# MI0283QT_v13.net
KiCad netlist of a schematic drawn in EAGLE
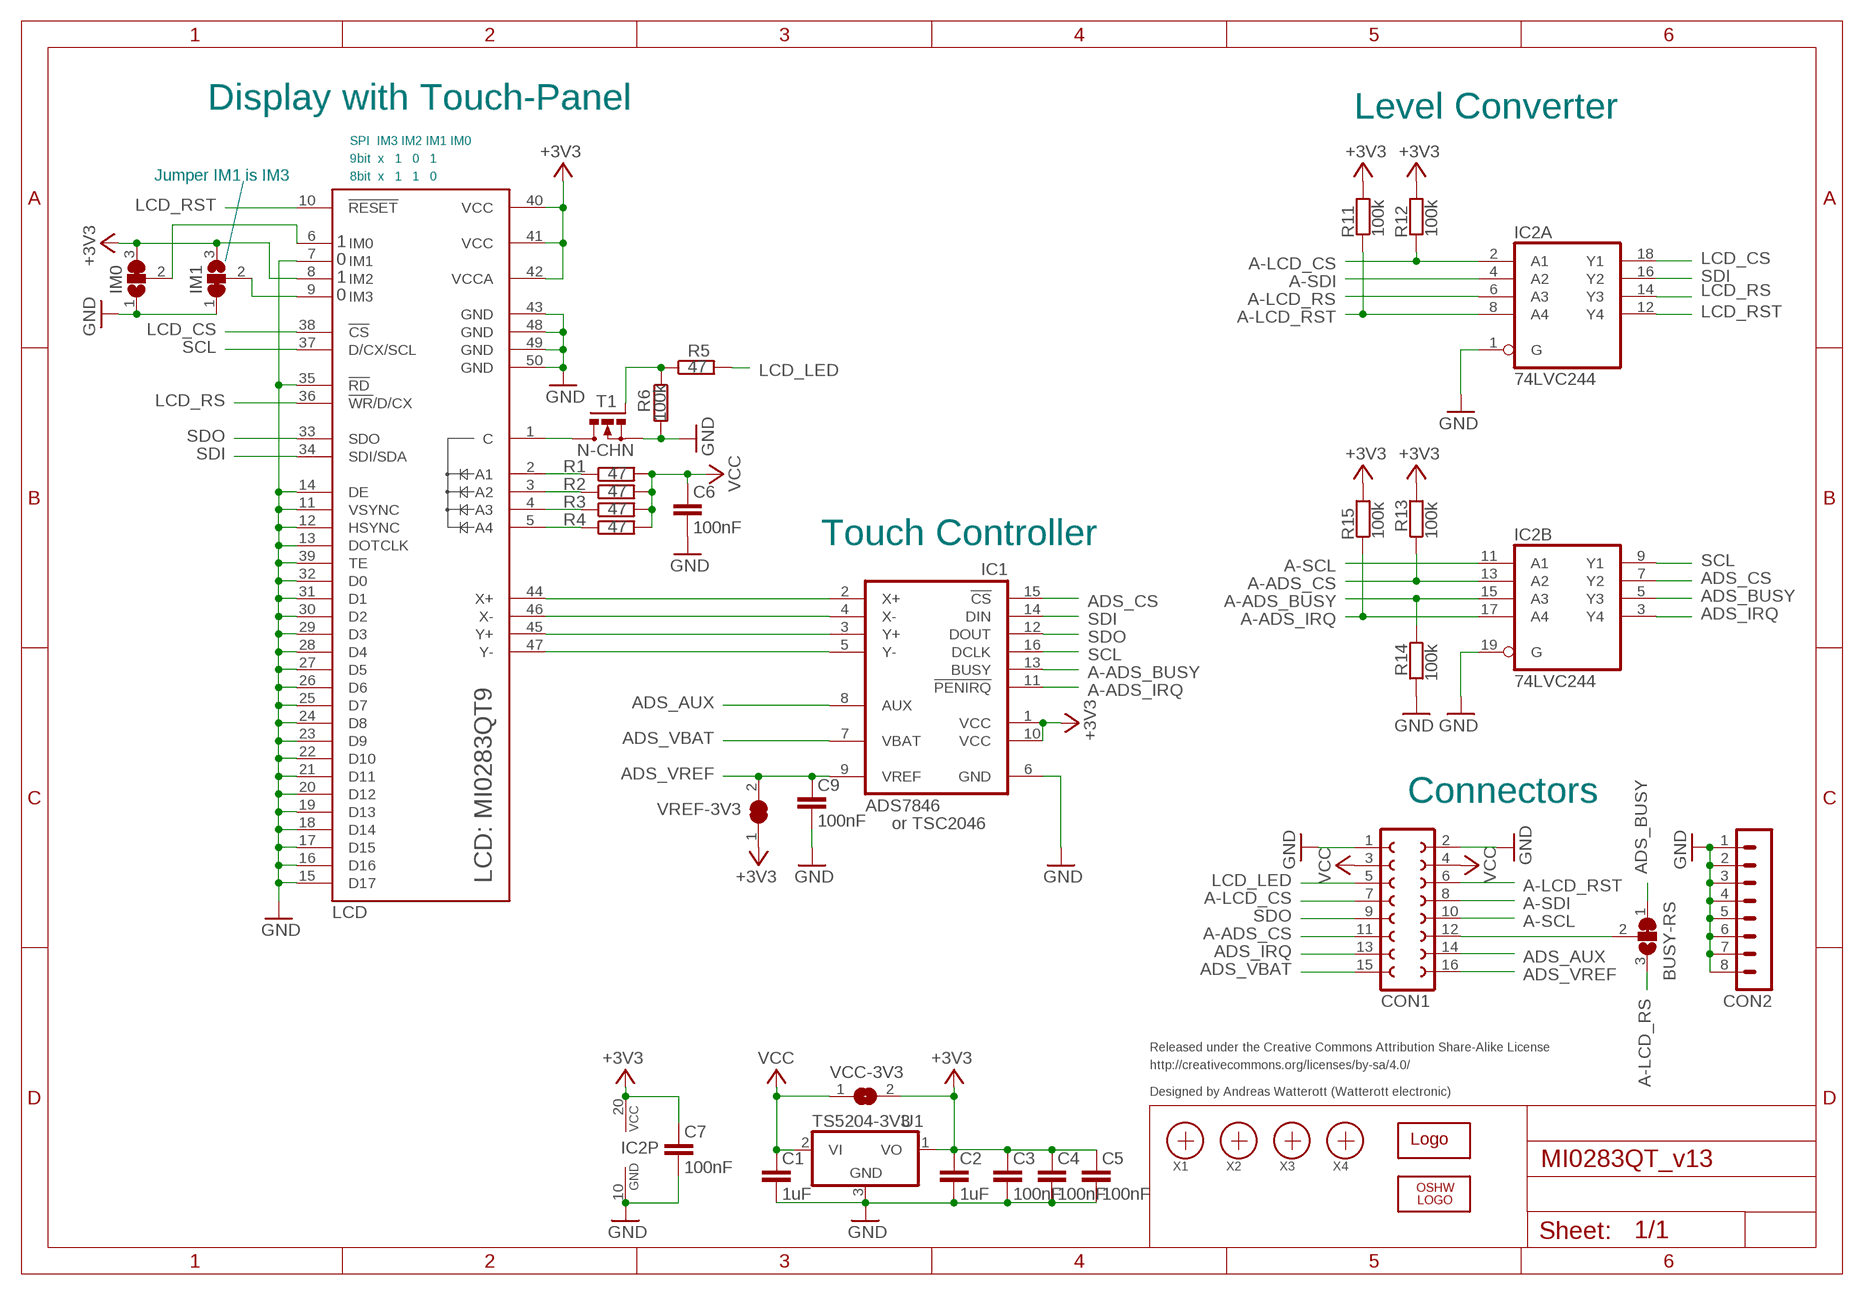
[diagram p0: schematic, sheet 1]

(export (version "E")
  (design (tool "Eeschema 10.0.6"))
  (components
    (comp (ref "BUSY-RS")
      (value "SJ2W")
      (footprint "eagle-import:SJ_2")
      (libsource (lib "eagle-import") (part "SJ2W"))
    )
    (comp (ref "C1")
      (value "1uF")
      (footprint "eagle-import:C0603")
      (libsource (lib "eagle-import") (part "C-EUC0603"))
    )
    (comp (ref "C2")
      (value "1uF")
      (footprint "eagle-import:C0603")
      (libsource (lib "eagle-import") (part "C-EUC0603"))
    )
    (comp (ref "C3")
      (value "100nF")
      (footprint "eagle-import:C0603")
      (libsource (lib "eagle-import") (part "C-EUC0603"))
    )
    (comp (ref "C4")
      (value "100nF")
      (footprint "eagle-import:C0603")
      (libsource (lib "eagle-import") (part "C-EUC0603"))
    )
    (comp (ref "C5")
      (value "100nF")
      (footprint "eagle-import:C0603")
      (libsource (lib "eagle-import") (part "C-EUC0603"))
    )
    (comp (ref "C6")
      (value "100nF")
      (footprint "eagle-import:C0603")
      (libsource (lib "eagle-import") (part "C-EUC0603"))
    )
    (comp (ref "C7")
      (value "100nF")
      (footprint "eagle-import:C0603")
      (libsource (lib "eagle-import") (part "C-EUC0603"))
    )
    (comp (ref "C9")
      (value "100nF")
      (footprint "eagle-import:C0603")
      (libsource (lib "eagle-import") (part "C-EUC0603"))
    )
    (comp (ref "CON1")
      (value "FE08-2")
      (footprint "eagle-import:FE08-2")
      (libsource (lib "eagle-import") (part "FE08-2"))
    )
    (comp (ref "CON2")
      (value "MA08-1")
      (footprint "eagle-import:MA08-1")
      (libsource (lib "eagle-import") (part "MA08-1"))
    )
    (comp (ref "IC1")
      (value "ADS7846")
      (footprint "eagle-import:SSOP16")
      (libsource (lib "eagle-import") (part "ADS7846"))
    )
    (comp (ref "IC2")
      (value "74LVC244")
      (footprint "eagle-import:SO20W")
      (libsource (lib "eagle-import") (part "74244DWHC"))
    )
    (comp (ref "IM0")
      (value "SJ2W")
      (footprint "eagle-import:SJ_2")
      (libsource (lib "eagle-import") (part "SJ2W"))
    )
    (comp (ref "IM1")
      (value "SJ2W")
      (footprint "eagle-import:SJ_2")
      (libsource (lib "eagle-import") (part "SJ2W"))
    )
    (comp (ref "LCD")
      (value "MI0283QT9")
      (footprint "eagle-import:MI0283QT9")
      (libsource (lib "eagle-import") (part "MI0283QT9"))
    )
    (comp (ref "LOGO1")
      (value "OSHW_LOGO_6MILX0150-NT")
      (footprint "eagle-import:OSHW_6X150_NOTEXT")
      (libsource (lib "eagle-import") (part "OSHW_LOGO_6MILX0150-NT"))
    )
    (comp (ref "R1")
      (value "47")
      (footprint "eagle-import:R0603")
      (libsource (lib "eagle-import") (part "R-EU_R0603"))
    )
    (comp (ref "R2")
      (value "47")
      (footprint "eagle-import:R0603")
      (libsource (lib "eagle-import") (part "R-EU_R0603"))
    )
    (comp (ref "R3")
      (value "47")
      (footprint "eagle-import:R0603")
      (libsource (lib "eagle-import") (part "R-EU_R0603"))
    )
    (comp (ref "R4")
      (value "47")
      (footprint "eagle-import:R0603")
      (libsource (lib "eagle-import") (part "R-EU_R0603"))
    )
    (comp (ref "R5")
      (value "47")
      (footprint "eagle-import:R0603")
      (libsource (lib "eagle-import") (part "R-EU_R0603"))
    )
    (comp (ref "R6")
      (value "100k")
      (footprint "eagle-import:R0603")
      (libsource (lib "eagle-import") (part "R-EU_R0603"))
    )
    (comp (ref "R11")
      (value "100k")
      (footprint "eagle-import:R0603")
      (libsource (lib "eagle-import") (part "R-EU_R0603"))
    )
    (comp (ref "R12")
      (value "100k")
      (footprint "eagle-import:R0603")
      (libsource (lib "eagle-import") (part "R-EU_R0603"))
    )
    (comp (ref "R13")
      (value "100k")
      (footprint "eagle-import:R0603")
      (libsource (lib "eagle-import") (part "R-EU_R0603"))
    )
    (comp (ref "R14")
      (value "100k")
      (footprint "eagle-import:R0603")
      (libsource (lib "eagle-import") (part "R-EU_R0603"))
    )
    (comp (ref "R15")
      (value "100k")
      (footprint "eagle-import:R0603")
      (libsource (lib "eagle-import") (part "R-EU_R0603"))
    )
    (comp (ref "T1")
      (value "N-CHN")
      (footprint "eagle-import:MICRO3")
      (libsource (lib "eagle-import") (part "IRLML2502"))
    )
    (comp (ref "U$1")
      (value "WE-LOGO")
      (footprint "eagle-import:WE-LOGO")
      (libsource (lib "eagle-import") (part "WE-LOGOPLACE"))
    )
    (comp (ref "U1")
      (value "TS5204-3V3")
      (footprint "eagle-import:SOT23")
      (libsource (lib "eagle-import") (part "TS5204"))
    )
    (comp (ref "VCC-3V3")
      (value "SJ")
      (footprint "eagle-import:SJ")
      (libsource (lib "eagle-import") (part "SJ"))
    )
    (comp (ref "VREF-3V3")
      (value "SJ")
      (footprint "eagle-import:SJ")
      (libsource (lib "eagle-import") (part "SJ"))
    )
    (comp (ref "X1")
      (value "PASSER")
      (footprint "eagle-import:PASSER")
      (libsource (lib "eagle-import") (part "PASSER"))
    )
    (comp (ref "X2")
      (value "PASSER")
      (footprint "eagle-import:PASSER")
      (libsource (lib "eagle-import") (part "PASSER"))
    )
    (comp (ref "X3")
      (value "PASSER")
      (footprint "eagle-import:PASSER")
      (libsource (lib "eagle-import") (part "PASSER"))
    )
    (comp (ref "X4")
      (value "PASSER")
      (footprint "eagle-import:PASSER")
      (libsource (lib "eagle-import") (part "PASSER"))
    )
  )
  (nets
    (net (code "1") (name "+3V3") (class "Default")
      (node (ref "C2") (pin "1") (pinfunction "1_1") (pintype "passive"))
      (node (ref "C3") (pin "1") (pinfunction "1_1") (pintype "passive"))
      (node (ref "C4") (pin "1") (pinfunction "1_1") (pintype "passive"))
      (node (ref "C5") (pin "1") (pinfunction "1_1") (pintype "passive"))
      (node (ref "C7") (pin "1") (pinfunction "1_1") (pintype "passive"))
      (node (ref "IC1") (pin "1") (pinfunction "VCC_1") (pintype "power_in"))
      (node (ref "IC1") (pin "10") (pinfunction "VCC_10") (pintype "power_in"))
      (node (ref "IC2") (pin "20") (pinfunction "VCC_20") (pintype "power_in"))
      (node (ref "IM0") (pin "3") (pinfunction "3_3") (pintype "passive"))
      (node (ref "IM1") (pin "3") (pinfunction "3_3") (pintype "passive"))
      (node (ref "LCD") (pin "40") (pinfunction "VCC_40") (pintype "power_in"))
      (node (ref "LCD") (pin "41") (pinfunction "VCC_41") (pintype "power_in"))
      (node (ref "LCD") (pin "42") (pinfunction "VCCA_42") (pintype "power_in"))
      (node (ref "LCD") (pin "8") (pinfunction "IM2_8") (pintype "input"))
      (node (ref "R11") (pin "2") (pinfunction "2_2") (pintype "passive"))
      (node (ref "R12") (pin "2") (pinfunction "2_2") (pintype "passive"))
      (node (ref "R13") (pin "2") (pinfunction "2_2") (pintype "passive"))
      (node (ref "R15") (pin "2") (pinfunction "2_2") (pintype "passive"))
      (node (ref "U1") (pin "1") (pinfunction "VO_1") (pintype "passive"))
      (node (ref "VCC-3V3") (pin "2") (pinfunction "2_2") (pintype "passive"))
      (node (ref "VREF-3V3") (pin "1") (pinfunction "1_1") (pintype "passive"))
    )
    (net (code "2") (name "/A-ADS_BUSY") (class "Default")
      (node (ref "IC1") (pin "13") (pinfunction "BUSY_13") (pintype "output"))
      (node (ref "IC2") (pin "15") (pinfunction "A3_15") (pintype "input"))
      (node (ref "R14") (pin "1") (pinfunction "1_1") (pintype "passive"))
    )
    (net (code "3") (name "/A-ADS_CS") (class "Default")
      (node (ref "CON1") (pin "11") (pinfunction "11_11") (pintype "passive"))
      (node (ref "IC2") (pin "13") (pinfunction "A2_13") (pintype "input"))
      (node (ref "R13") (pin "1") (pinfunction "1_1") (pintype "passive"))
    )
    (net (code "4") (name "/A-ADS_IRQ") (class "Default")
      (node (ref "IC1") (pin "11") (pinfunction "~{PENIRQ}_11") (pintype "output"))
      (node (ref "IC2") (pin "17") (pinfunction "A4_17") (pintype "input"))
      (node (ref "R15") (pin "1") (pinfunction "1_1") (pintype "passive"))
    )
    (net (code "5") (name "/A-LCD_CS") (class "Default")
      (node (ref "CON1") (pin "7") (pinfunction "7_7") (pintype "passive"))
      (node (ref "IC2") (pin "2") (pinfunction "A1_2") (pintype "input"))
      (node (ref "R12") (pin "1") (pinfunction "1_1") (pintype "passive"))
    )
    (net (code "6") (name "/A-LCD_RS") (class "Default")
      (node (ref "BUSY-RS") (pin "3") (pinfunction "3_3") (pintype "passive"))
      (node (ref "IC2") (pin "6") (pinfunction "A3_6") (pintype "input"))
    )
    (net (code "7") (name "/A-LCD_RST") (class "Default")
      (node (ref "CON1") (pin "6") (pinfunction "6_6") (pintype "passive"))
      (node (ref "IC2") (pin "8") (pinfunction "A4_8") (pintype "input"))
      (node (ref "R11") (pin "1") (pinfunction "1_1") (pintype "passive"))
    )
    (net (code "8") (name "/A-SCL") (class "Default")
      (node (ref "CON1") (pin "10") (pinfunction "10_10") (pintype "passive"))
      (node (ref "IC2") (pin "11") (pinfunction "A1_11") (pintype "input"))
    )
    (net (code "9") (name "/A-SDI") (class "Default")
      (node (ref "CON1") (pin "8") (pinfunction "8_8") (pintype "passive"))
      (node (ref "IC2") (pin "4") (pinfunction "A2_4") (pintype "input"))
    )
    (net (code "10") (name "/ADS_AUX") (class "Default")
      (node (ref "CON1") (pin "14") (pinfunction "14_14") (pintype "passive"))
      (node (ref "IC1") (pin "8") (pinfunction "AUX_8") (pintype "input"))
    )
    (net (code "11") (name "/ADS_BUSY") (class "Default")
      (node (ref "BUSY-RS") (pin "1") (pinfunction "1_1") (pintype "passive"))
      (node (ref "IC2") (pin "5") (pinfunction "Y3_5") (pintype "tri_state"))
    )
    (net (code "12") (name "/ADS_CS") (class "Default")
      (node (ref "IC1") (pin "15") (pinfunction "~{CS}_15") (pintype "input"))
      (node (ref "IC2") (pin "7") (pinfunction "Y2_7") (pintype "tri_state"))
    )
    (net (code "13") (name "/ADS_IRQ") (class "Default")
      (node (ref "CON1") (pin "13") (pinfunction "13_13") (pintype "passive"))
      (node (ref "IC2") (pin "3") (pinfunction "Y4_3") (pintype "tri_state"))
    )
    (net (code "14") (name "/ADS_VBAT") (class "Default")
      (node (ref "CON1") (pin "15") (pinfunction "15_15") (pintype "passive"))
      (node (ref "IC1") (pin "7") (pinfunction "VBAT_7") (pintype "input"))
    )
    (net (code "15") (name "/ADS_VREF") (class "Default")
      (node (ref "C9") (pin "1") (pinfunction "1_1") (pintype "passive"))
      (node (ref "CON1") (pin "16") (pinfunction "16_16") (pintype "passive"))
      (node (ref "IC1") (pin "9") (pinfunction "VREF_9") (pintype "bidirectional"))
      (node (ref "VREF-3V3") (pin "2") (pinfunction "2_2") (pintype "passive"))
    )
    (net (code "16") (name "/LCD_CS") (class "Default")
      (node (ref "IC2") (pin "18") (pinfunction "Y1_18") (pintype "tri_state"))
      (node (ref "LCD") (pin "38") (pinfunction "~{CS}_38") (pintype "input"))
    )
    (net (code "17") (name "/LCD_LED") (class "Default")
      (node (ref "CON1") (pin "5") (pinfunction "5_5") (pintype "passive"))
      (node (ref "R5") (pin "2") (pinfunction "2_2") (pintype "passive"))
    )
    (net (code "18") (name "/LCD_RS") (class "Default")
      (node (ref "IC2") (pin "14") (pinfunction "Y3_14") (pintype "tri_state"))
      (node (ref "LCD") (pin "36") (pinfunction "~{WR}/D/CX_36") (pintype "input"))
    )
    (net (code "19") (name "/LCD_RST") (class "Default")
      (node (ref "IC2") (pin "12") (pinfunction "Y4_12") (pintype "tri_state"))
      (node (ref "LCD") (pin "10") (pinfunction "~{RESET}_10") (pintype "input"))
    )
    (net (code "20") (name "/SCL") (class "Default")
      (node (ref "IC1") (pin "16") (pinfunction "DCLK_16") (pintype "output"))
      (node (ref "IC2") (pin "9") (pinfunction "Y1_9") (pintype "tri_state"))
      (node (ref "LCD") (pin "37") (pinfunction "D/CX/SCL_37") (pintype "input"))
    )
    (net (code "21") (name "/SDI") (class "Default")
      (node (ref "IC1") (pin "14") (pinfunction "DIN_14") (pintype "input"))
      (node (ref "IC2") (pin "16") (pinfunction "Y2_16") (pintype "tri_state"))
      (node (ref "LCD") (pin "34") (pinfunction "SDI/SDA_34") (pintype "input"))
    )
    (net (code "22") (name "/SDO") (class "Default")
      (node (ref "CON1") (pin "9") (pinfunction "9_9") (pintype "passive"))
      (node (ref "IC1") (pin "12") (pinfunction "DOUT_12") (pintype "input"))
      (node (ref "LCD") (pin "33") (pinfunction "SDO_33") (pintype "output"))
    )
    (net (code "23") (name "GND") (class "Default")
      (node (ref "C1") (pin "2") (pinfunction "2_2") (pintype "passive"))
      (node (ref "C2") (pin "2") (pinfunction "2_2") (pintype "passive"))
      (node (ref "C3") (pin "2") (pinfunction "2_2") (pintype "passive"))
      (node (ref "C4") (pin "2") (pinfunction "2_2") (pintype "passive"))
      (node (ref "C5") (pin "2") (pinfunction "2_2") (pintype "passive"))
      (node (ref "C6") (pin "2") (pinfunction "2_2") (pintype "passive"))
      (node (ref "C7") (pin "2") (pinfunction "2_2") (pintype "passive"))
      (node (ref "C9") (pin "2") (pinfunction "2_2") (pintype "passive"))
      (node (ref "CON1") (pin "1") (pinfunction "1_1") (pintype "passive"))
      (node (ref "CON1") (pin "2") (pinfunction "2_2") (pintype "passive"))
      (node (ref "CON2") (pin "1") (pinfunction "1_1") (pintype "passive"))
      (node (ref "CON2") (pin "2") (pinfunction "2_2") (pintype "passive"))
      (node (ref "CON2") (pin "3") (pinfunction "3_3") (pintype "passive"))
      (node (ref "CON2") (pin "4") (pinfunction "4_4") (pintype "passive"))
      (node (ref "CON2") (pin "5") (pinfunction "5_5") (pintype "passive"))
      (node (ref "CON2") (pin "6") (pinfunction "6_6") (pintype "passive"))
      (node (ref "CON2") (pin "7") (pinfunction "7_7") (pintype "passive"))
      (node (ref "CON2") (pin "8") (pinfunction "8_8") (pintype "passive"))
      (node (ref "IC1") (pin "6") (pinfunction "GND_6") (pintype "power_in"))
      (node (ref "IC2") (pin "1") (pinfunction "G_1") (pintype "input"))
      (node (ref "IC2") (pin "10") (pinfunction "GND_10") (pintype "power_in"))
      (node (ref "IC2") (pin "19") (pinfunction "G_19") (pintype "input"))
      (node (ref "IM0") (pin "1") (pinfunction "1_1") (pintype "passive"))
      (node (ref "IM1") (pin "1") (pinfunction "1_1") (pintype "passive"))
      (node (ref "LCD") (pin "11") (pinfunction "VSYNC_11") (pintype "input"))
      (node (ref "LCD") (pin "12") (pinfunction "HSYNC_12") (pintype "input"))
      (node (ref "LCD") (pin "13") (pinfunction "DOTCLK_13") (pintype "input"))
      (node (ref "LCD") (pin "14") (pinfunction "DE_14") (pintype "input"))
      (node (ref "LCD") (pin "15") (pinfunction "D17_15") (pintype "input"))
      (node (ref "LCD") (pin "16") (pinfunction "D16_16") (pintype "input"))
      (node (ref "LCD") (pin "17") (pinfunction "D15_17") (pintype "input"))
      (node (ref "LCD") (pin "18") (pinfunction "D14_18") (pintype "input"))
      (node (ref "LCD") (pin "19") (pinfunction "D13_19") (pintype "input"))
      (node (ref "LCD") (pin "20") (pinfunction "D12_20") (pintype "input"))
      (node (ref "LCD") (pin "21") (pinfunction "D11_21") (pintype "input"))
      (node (ref "LCD") (pin "22") (pinfunction "D10_22") (pintype "input"))
      (node (ref "LCD") (pin "23") (pinfunction "D9_23") (pintype "input"))
      (node (ref "LCD") (pin "24") (pinfunction "D8_24") (pintype "input"))
      (node (ref "LCD") (pin "25") (pinfunction "D7_25") (pintype "input"))
      (node (ref "LCD") (pin "26") (pinfunction "D6_26") (pintype "input"))
      (node (ref "LCD") (pin "27") (pinfunction "D5_27") (pintype "input"))
      (node (ref "LCD") (pin "28") (pinfunction "D4_28") (pintype "input"))
      (node (ref "LCD") (pin "29") (pinfunction "D3_29") (pintype "input"))
      (node (ref "LCD") (pin "30") (pinfunction "D2_30") (pintype "input"))
      (node (ref "LCD") (pin "31") (pinfunction "D1_31") (pintype "input"))
      (node (ref "LCD") (pin "32") (pinfunction "D0_32") (pintype "input"))
      (node (ref "LCD") (pin "35") (pinfunction "~{RD}_35") (pintype "input"))
      (node (ref "LCD") (pin "39") (pinfunction "TE_39") (pintype "output"))
      (node (ref "LCD") (pin "43") (pinfunction "GND_43") (pintype "power_in"))
      (node (ref "LCD") (pin "48") (pinfunction "GND_48") (pintype "power_in"))
      (node (ref "LCD") (pin "49") (pinfunction "GND_49") (pintype "power_in"))
      (node (ref "LCD") (pin "50") (pinfunction "GND_50") (pintype "power_in"))
      (node (ref "LCD") (pin "7") (pinfunction "IM1_7") (pintype "input"))
      (node (ref "R14") (pin "2") (pinfunction "2_2") (pintype "passive"))
      (node (ref "R6") (pin "2") (pinfunction "2_2") (pintype "passive"))
      (node (ref "T1") (pin "2") (pinfunction "S_2") (pintype "passive"))
      (node (ref "U1") (pin "3") (pinfunction "GND_3") (pintype "passive"))
    )
    (net (code "24") (name "Net-(BUSY-RS-Pad2)") (class "Default")
      (node (ref "BUSY-RS") (pin "2") (pinfunction "2_2") (pintype "passive"))
      (node (ref "CON1") (pin "12") (pinfunction "12_12") (pintype "passive"))
    )
    (net (code "25") (name "Net-(IC1-X+)") (class "Default")
      (node (ref "IC1") (pin "2") (pinfunction "X+_2") (pintype "input"))
      (node (ref "LCD") (pin "44") (pinfunction "X+_44") (pintype "passive"))
    )
    (net (code "26") (name "Net-(IC1-X-)") (class "Default")
      (node (ref "IC1") (pin "4") (pinfunction "X-_4") (pintype "input"))
      (node (ref "LCD") (pin "46") (pinfunction "X-_46") (pintype "passive"))
    )
    (net (code "27") (name "Net-(IC1-Y+)") (class "Default")
      (node (ref "IC1") (pin "3") (pinfunction "Y+_3") (pintype "input"))
      (node (ref "LCD") (pin "45") (pinfunction "Y+_45") (pintype "passive"))
    )
    (net (code "28") (name "Net-(IC1-Y-)") (class "Default")
      (node (ref "IC1") (pin "5") (pinfunction "Y-_5") (pintype "input"))
      (node (ref "LCD") (pin "47") (pinfunction "Y-_47") (pintype "passive"))
    )
    (net (code "29") (name "Net-(LCD-A1)") (class "Default")
      (node (ref "LCD") (pin "2") (pinfunction "A1_2") (pintype "power_in"))
      (node (ref "R1") (pin "1") (pinfunction "1_1") (pintype "passive"))
    )
    (net (code "30") (name "Net-(LCD-A2)") (class "Default")
      (node (ref "LCD") (pin "3") (pinfunction "A2_3") (pintype "power_in"))
      (node (ref "R2") (pin "1") (pinfunction "1_1") (pintype "passive"))
    )
    (net (code "31") (name "Net-(LCD-A3)") (class "Default")
      (node (ref "LCD") (pin "4") (pinfunction "A3_4") (pintype "power_in"))
      (node (ref "R3") (pin "1") (pinfunction "1_1") (pintype "passive"))
    )
    (net (code "32") (name "Net-(LCD-A4)") (class "Default")
      (node (ref "LCD") (pin "5") (pinfunction "A4_5") (pintype "power_in"))
      (node (ref "R4") (pin "1") (pinfunction "1_1") (pintype "passive"))
    )
    (net (code "33") (name "Net-(LCD-C)") (class "Default")
      (node (ref "LCD") (pin "1") (pinfunction "C_1") (pintype "power_in"))
      (node (ref "T1") (pin "3") (pinfunction "D_3") (pintype "passive"))
    )
    (net (code "34") (name "Net-(LCD-IM0)") (class "Default")
      (node (ref "IM0") (pin "2") (pinfunction "2_2") (pintype "passive"))
      (node (ref "LCD") (pin "6") (pinfunction "IM0_6") (pintype "input"))
    )
    (net (code "35") (name "Net-(LCD-IM3)") (class "Default")
      (node (ref "IM1") (pin "2") (pinfunction "2_2") (pintype "passive"))
      (node (ref "LCD") (pin "9") (pinfunction "IM3_9") (pintype "input"))
    )
    (net (code "36") (name "Net-(T1-G)") (class "Default")
      (node (ref "R5") (pin "1") (pinfunction "1_1") (pintype "passive"))
      (node (ref "R6") (pin "1") (pinfunction "1_1") (pintype "passive"))
      (node (ref "T1") (pin "1") (pinfunction "G_1") (pintype "passive"))
    )
    (net (code "37") (name "VCC") (class "Default")
      (node (ref "C1") (pin "1") (pinfunction "1_1") (pintype "passive"))
      (node (ref "C6") (pin "1") (pinfunction "1_1") (pintype "passive"))
      (node (ref "CON1") (pin "3") (pinfunction "3_3") (pintype "passive"))
      (node (ref "CON1") (pin "4") (pinfunction "4_4") (pintype "passive"))
      (node (ref "R1") (pin "2") (pinfunction "2_2") (pintype "passive"))
      (node (ref "R2") (pin "2") (pinfunction "2_2") (pintype "passive"))
      (node (ref "R3") (pin "2") (pinfunction "2_2") (pintype "passive"))
      (node (ref "R4") (pin "2") (pinfunction "2_2") (pintype "passive"))
      (node (ref "U1") (pin "2") (pinfunction "VI_2") (pintype "input"))
      (node (ref "VCC-3V3") (pin "1") (pinfunction "1_1") (pintype "passive"))
    )
  )
)
